# counter_defender_mk_3.net
KiCad netlist of a schematic drawn in EAGLE
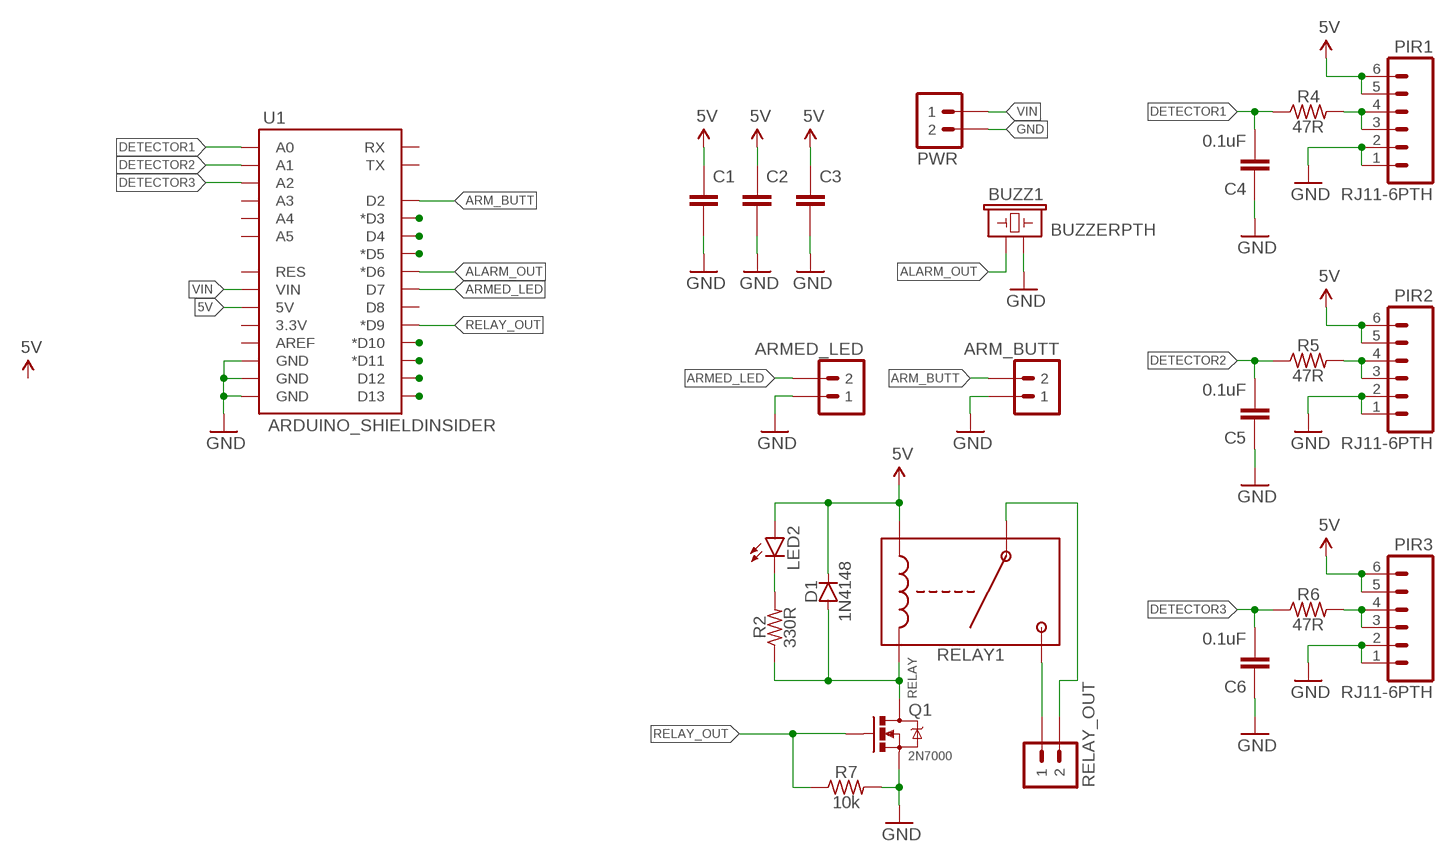
[diagram p0: schematic, sheet 1]

(export (version "E")
  (design (tool "Eeschema 10.0.6"))
  (components
    (comp (ref "ARMED_LED")
      (value "M02JST-PTH-VERT")
      (footprint "eagle-import:JST-2-PH-VERT-PTH")
      (libsource (lib "eagle-import") (part "M02JST-PTH-VERT"))
    )
    (comp (ref "ARM_BUTT")
      (value "M02JST-PTH-VERT")
      (footprint "eagle-import:JST-2-PH-VERT-PTH")
      (libsource (lib "eagle-import") (part "M02JST-PTH-VERT"))
    )
    (comp (ref "BUZZ1")
      (value "BUZZERPTH")
      (footprint "eagle-import:BUZZER-12MM")
      (libsource (lib "eagle-import") (part "BUZZERPTH"))
    )
    (comp (ref "C1")
      (value "CAPACITOR-CERAMIC025-024X044")
      (footprint "eagle-import:C025-024X044")
      (libsource (lib "eagle-import") (part "CAPACITOR-CERAMIC025-024X044"))
    )
    (comp (ref "C2")
      (value "CAPACITOR-CERAMIC025-024X044")
      (footprint "eagle-import:C025-024X044")
      (libsource (lib "eagle-import") (part "CAPACITOR-CERAMIC025-024X044"))
    )
    (comp (ref "C3")
      (value "CAPACITOR-CERAMIC025-024X044")
      (footprint "eagle-import:C025-024X044")
      (libsource (lib "eagle-import") (part "CAPACITOR-CERAMIC025-024X044"))
    )
    (comp (ref "C4")
      (value "0.1uF")
      (footprint "eagle-import:C025-024X044")
      (libsource (lib "eagle-import") (part "CAPACITOR-CERAMIC025-024X044"))
    )
    (comp (ref "C5")
      (value "0.1uF")
      (footprint "eagle-import:C025-024X044")
      (libsource (lib "eagle-import") (part "CAPACITOR-CERAMIC025-024X044"))
    )
    (comp (ref "C6")
      (value "0.1uF")
      (footprint "eagle-import:C025-024X044")
      (libsource (lib "eagle-import") (part "CAPACITOR-CERAMIC025-024X044"))
    )
    (comp (ref "D1")
      (value "1N4148")
      (footprint "eagle-import:DIODE-7.62MM")
      (libsource (lib "eagle-import") (part "DIODEPTH-7.62MM"))
    )
    (comp (ref "LED2")
      (value "LED3MM")
      (footprint "eagle-import:LED3MM")
      (libsource (lib "eagle-import") (part "LED3MM"))
    )
    (comp (ref "PIR1")
      (value "RJ11-6PTH")
      (footprint "eagle-import:RJ11-6")
      (libsource (lib "eagle-import") (part "RJ11-6PTH"))
    )
    (comp (ref "PIR2")
      (value "RJ11-6PTH")
      (footprint "eagle-import:RJ11-6")
      (libsource (lib "eagle-import") (part "RJ11-6PTH"))
    )
    (comp (ref "PIR3")
      (value "RJ11-6PTH")
      (footprint "eagle-import:RJ11-6")
      (libsource (lib "eagle-import") (part "RJ11-6PTH"))
    )
    (comp (ref "PWR")
      (value "M02JST-PTH-VERT")
      (footprint "eagle-import:JST-2-PH-VERT-PTH")
      (libsource (lib "eagle-import") (part "M02JST-PTH-VERT"))
    )
    (comp (ref "Q1")
      (value "2N7000")
      (footprint "eagle-import:TO-92-AMMO")
      (libsource (lib "eagle-import") (part "MOSFET-NCHANNEL2N7000-AMMO"))
    )
    (comp (ref "R2")
      (value "330R")
      (footprint "eagle-import:RESISTOR-AXIAL-PTH-7.62MM")
      (libsource (lib "eagle-import") (part "RESISTORPTH-AXIAL-7.62MM"))
    )
    (comp (ref "R4")
      (value "47R")
      (footprint "eagle-import:RESISTOR-AXIAL-PTH-6.35MM")
      (libsource (lib "eagle-import") (part "RESISTORPTH-AXIAL-6.35MM"))
    )
    (comp (ref "R5")
      (value "47R")
      (footprint "eagle-import:RESISTOR-AXIAL-PTH-6.35MM")
      (libsource (lib "eagle-import") (part "RESISTORPTH-AXIAL-6.35MM"))
    )
    (comp (ref "R6")
      (value "47R")
      (footprint "eagle-import:RESISTOR-AXIAL-PTH-6.35MM")
      (libsource (lib "eagle-import") (part "RESISTORPTH-AXIAL-6.35MM"))
    )
    (comp (ref "R7")
      (value "10k")
      (footprint "eagle-import:RESISTOR-AXIAL-PTH-7.62MM")
      (libsource (lib "eagle-import") (part "RESISTORPTH-AXIAL-7.62MM"))
    )
    (comp (ref "RELAY1")
      (value "RELAY-SPST-NOT77")
      (footprint "eagle-import:T77-SPST-NO-RELAY")
      (libsource (lib "eagle-import") (part "RELAY-SPST-NOT77"))
    )
    (comp (ref "RELAY_OUT")
      (value "M02SCREWTERM_2.54MM")
      (footprint "eagle-import:1X02_2.54_SCREWTERM")
      (libsource (lib "eagle-import") (part "M02SCREWTERM_2.54MM"))
    )
    (comp (ref "U1")
      (value "ARDUINO_SHIELDINSIDER")
      (footprint "eagle-import:ARDUINO_SHIELD_NOOUTLINE_INSIDE")
      (libsource (lib "eagle-import") (part "ARDUINO_SHIELDINSIDER"))
    )
  )
  (nets
    (net (code "1") (name "/RELAY") (class "Default")
      (node (ref "D1") (pin "A") (pinfunction "A_A") (pintype "passive"))
      (node (ref "Q1") (pin "3") (pinfunction "D_3") (pintype "passive"))
      (node (ref "R2") (pin "P$1") (pinfunction "1_P$1") (pintype "passive"))
      (node (ref "RELAY1") (pin "COIL1") (pinfunction "C$1_COIL1") (pintype "bidirectional"))
    )
    (net (code "2") (name "5V") (class "Default")
      (node (ref "C1") (pin "1") (pinfunction "1_1") (pintype "passive"))
      (node (ref "C2") (pin "1") (pinfunction "1_1") (pintype "passive"))
      (node (ref "C3") (pin "1") (pinfunction "1_1") (pintype "passive"))
      (node (ref "D1") (pin "K") (pinfunction "C_K") (pintype "passive"))
      (node (ref "LED2") (pin "A") (pinfunction "A_A") (pintype "passive"))
      (node (ref "PIR1") (pin "5") (pinfunction "5_5") (pintype "passive"))
      (node (ref "PIR1") (pin "6") (pinfunction "6_6") (pintype "passive"))
      (node (ref "PIR2") (pin "5") (pinfunction "5_5") (pintype "passive"))
      (node (ref "PIR2") (pin "6") (pinfunction "6_6") (pintype "passive"))
      (node (ref "PIR3") (pin "5") (pinfunction "5_5") (pintype "passive"))
      (node (ref "PIR3") (pin "6") (pinfunction "6_6") (pintype "passive"))
      (node (ref "RELAY1") (pin "COIL2") (pinfunction "C$2_COIL2") (pintype "bidirectional"))
      (node (ref "U1") (pin "5V") (pinfunction "5V_5V") (pintype "bidirectional"))
    )
    (net (code "3") (name "ALARM_OUT") (class "Default")
      (node (ref "BUZZ1") (pin "+") (pinfunction "1_+") (pintype "passive"))
      (node (ref "U1") (pin "D6") (pinfunction "*D6_D6") (pintype "bidirectional"))
    )
    (net (code "4") (name "ARMED_LED") (class "Default")
      (node (ref "ARMED_LED") (pin "2") (pinfunction "2_2") (pintype "passive"))
      (node (ref "U1") (pin "D7") (pinfunction "D7_D7") (pintype "bidirectional"))
    )
    (net (code "5") (name "ARM_BUTT") (class "Default")
      (node (ref "ARM_BUTT") (pin "2") (pinfunction "2_2") (pintype "passive"))
      (node (ref "U1") (pin "D2") (pinfunction "D2_D2") (pintype "bidirectional"))
    )
    (net (code "6") (name "DETECTOR1") (class "Default")
      (node (ref "C4") (pin "2") (pinfunction "2_2") (pintype "passive"))
      (node (ref "R4") (pin "P$1") (pinfunction "1_P$1") (pintype "passive"))
      (node (ref "U1") (pin "A0") (pinfunction "A0_A0") (pintype "bidirectional"))
    )
    (net (code "7") (name "DETECTOR2") (class "Default")
      (node (ref "C5") (pin "2") (pinfunction "2_2") (pintype "passive"))
      (node (ref "R5") (pin "P$1") (pinfunction "1_P$1") (pintype "passive"))
      (node (ref "U1") (pin "A1") (pinfunction "A1_A1") (pintype "bidirectional"))
    )
    (net (code "8") (name "DETECTOR3") (class "Default")
      (node (ref "C6") (pin "2") (pinfunction "2_2") (pintype "passive"))
      (node (ref "R6") (pin "P$1") (pinfunction "1_P$1") (pintype "passive"))
      (node (ref "U1") (pin "A2") (pinfunction "A2_A2") (pintype "bidirectional"))
    )
    (net (code "9") (name "GND") (class "Default")
      (node (ref "ARMED_LED") (pin "1") (pinfunction "1_1") (pintype "passive"))
      (node (ref "ARM_BUTT") (pin "1") (pinfunction "1_1") (pintype "passive"))
      (node (ref "BUZZ1") (pin "-") (pinfunction "2_-") (pintype "passive"))
      (node (ref "C1") (pin "2") (pinfunction "2_2") (pintype "passive"))
      (node (ref "C2") (pin "2") (pinfunction "2_2") (pintype "passive"))
      (node (ref "C3") (pin "2") (pinfunction "2_2") (pintype "passive"))
      (node (ref "C4") (pin "1") (pinfunction "1_1") (pintype "passive"))
      (node (ref "C5") (pin "1") (pinfunction "1_1") (pintype "passive"))
      (node (ref "C6") (pin "1") (pinfunction "1_1") (pintype "passive"))
      (node (ref "PIR1") (pin "1") (pinfunction "1_1") (pintype "passive"))
      (node (ref "PIR1") (pin "2") (pinfunction "2_2") (pintype "passive"))
      (node (ref "PIR2") (pin "1") (pinfunction "1_1") (pintype "passive"))
      (node (ref "PIR2") (pin "2") (pinfunction "2_2") (pintype "passive"))
      (node (ref "PIR3") (pin "1") (pinfunction "1_1") (pintype "passive"))
      (node (ref "PIR3") (pin "2") (pinfunction "2_2") (pintype "passive"))
      (node (ref "PWR") (pin "2") (pinfunction "2_2") (pintype "passive"))
      (node (ref "Q1") (pin "1") (pinfunction "S_1") (pintype "passive"))
      (node (ref "R7") (pin "P$2") (pinfunction "2_P$2") (pintype "passive"))
      (node (ref "U1") (pin "GND@0") (pinfunction "GND_GND@0") (pintype "bidirectional"))
      (node (ref "U1") (pin "GND@1") (pinfunction "GND_GND@1") (pintype "bidirectional"))
      (node (ref "U1") (pin "GND@2") (pinfunction "GND_GND@2") (pintype "bidirectional"))
    )
    (net (code "10") (name "Net-(LED2-C)") (class "Default")
      (node (ref "LED2") (pin "K") (pinfunction "C_K") (pintype "passive"))
      (node (ref "R2") (pin "P$2") (pinfunction "2_P$2") (pintype "passive"))
    )
    (net (code "11") (name "Net-(R4-2)") (class "Default")
      (node (ref "PIR1") (pin "3") (pinfunction "3_3") (pintype "passive"))
      (node (ref "PIR1") (pin "4") (pinfunction "4_4") (pintype "passive"))
      (node (ref "R4") (pin "P$2") (pinfunction "2_P$2") (pintype "passive"))
    )
    (net (code "12") (name "Net-(R5-2)") (class "Default")
      (node (ref "PIR2") (pin "3") (pinfunction "3_3") (pintype "passive"))
      (node (ref "PIR2") (pin "4") (pinfunction "4_4") (pintype "passive"))
      (node (ref "R5") (pin "P$2") (pinfunction "2_P$2") (pintype "passive"))
    )
    (net (code "13") (name "Net-(R6-2)") (class "Default")
      (node (ref "PIR3") (pin "3") (pinfunction "3_3") (pintype "passive"))
      (node (ref "PIR3") (pin "4") (pinfunction "4_4") (pintype "passive"))
      (node (ref "R6") (pin "P$2") (pinfunction "2_P$2") (pintype "passive"))
    )
    (net (code "14") (name "Net-(RELAY_OUT-1)") (class "Default")
      (node (ref "RELAY1") (pin "NO") (pinfunction "NO_NO") (pintype "bidirectional"))
      (node (ref "RELAY_OUT") (pin "P1") (pinfunction "1_P1") (pintype "passive"))
    )
    (net (code "15") (name "Net-(RELAY_OUT-2)") (class "Default")
      (node (ref "RELAY1") (pin "COM") (pinfunction "COM_COM") (pintype "bidirectional"))
      (node (ref "RELAY_OUT") (pin "P2") (pinfunction "2_P2") (pintype "passive"))
    )
    (net (code "16") (name "RELAY_OUT") (class "Default")
      (node (ref "Q1") (pin "2") (pinfunction "G_2") (pintype "passive"))
      (node (ref "R7") (pin "P$1") (pinfunction "1_P$1") (pintype "passive"))
      (node (ref "U1") (pin "D9") (pinfunction "*D9_D9") (pintype "bidirectional"))
    )
    (net (code "17") (name "VIN") (class "Default")
      (node (ref "PWR") (pin "1") (pinfunction "1_1") (pintype "passive"))
      (node (ref "U1") (pin "VIN") (pinfunction "VIN_VIN") (pintype "bidirectional"))
    )
    (net (code "18") (name "unconnected-(U1-*D3-PadD3)") (class "Default")
      (node (ref "U1") (pin "D3") (pinfunction "*D3_D3") (pintype "bidirectional"))
    )
    (net (code "19") (name "unconnected-(U1-*D5-PadD5)") (class "Default")
      (node (ref "U1") (pin "D5") (pinfunction "*D5_D5") (pintype "bidirectional"))
    )
    (net (code "20") (name "unconnected-(U1-*D10-PadD10)") (class "Default")
      (node (ref "U1") (pin "D10") (pinfunction "*D10_D10") (pintype "bidirectional"))
    )
    (net (code "21") (name "unconnected-(U1-*D11-PadD11)") (class "Default")
      (node (ref "U1") (pin "D11") (pinfunction "*D11_D11") (pintype "bidirectional"))
    )
    (net (code "22") (name "unconnected-(U1-Pad3.3V)") (class "Default")
      (node (ref "U1") (pin "3.3V") (pinfunction "3.3V_3.3V") (pintype "bidirectional"))
    )
    (net (code "23") (name "unconnected-(U1-PadA3)") (class "Default")
      (node (ref "U1") (pin "A3") (pinfunction "A3_A3") (pintype "bidirectional"))
    )
    (net (code "24") (name "unconnected-(U1-PadA4)") (class "Default")
      (node (ref "U1") (pin "A4") (pinfunction "A4_A4") (pintype "bidirectional"))
    )
    (net (code "25") (name "unconnected-(U1-PadA5)") (class "Default")
      (node (ref "U1") (pin "A5") (pinfunction "A5_A5") (pintype "bidirectional"))
    )
    (net (code "26") (name "unconnected-(U1-PadAREF)") (class "Default")
      (node (ref "U1") (pin "AREF") (pinfunction "AREF_AREF") (pintype "bidirectional"))
    )
    (net (code "27") (name "unconnected-(U1-PadD4)") (class "Default")
      (node (ref "U1") (pin "D4") (pinfunction "D4_D4") (pintype "bidirectional"))
    )
    (net (code "28") (name "unconnected-(U1-PadD8)") (class "Default")
      (node (ref "U1") (pin "D8") (pinfunction "D8_D8") (pintype "bidirectional"))
    )
    (net (code "29") (name "unconnected-(U1-PadD12)") (class "Default")
      (node (ref "U1") (pin "D12") (pinfunction "D12_D12") (pintype "bidirectional"))
    )
    (net (code "30") (name "unconnected-(U1-PadD13)") (class "Default")
      (node (ref "U1") (pin "D13") (pinfunction "D13_D13") (pintype "bidirectional"))
    )
    (net (code "31") (name "unconnected-(U1-PadRES)") (class "Default")
      (node (ref "U1") (pin "RES") (pinfunction "RES_RES") (pintype "bidirectional"))
    )
    (net (code "32") (name "unconnected-(U1-PadRX)") (class "Default")
      (node (ref "U1") (pin "RX") (pinfunction "RX_RX") (pintype "bidirectional"))
    )
    (net (code "33") (name "unconnected-(U1-PadTX)") (class "Default")
      (node (ref "U1") (pin "TX") (pinfunction "TX_TX") (pintype "bidirectional"))
    )
  )
)
